# SpiderSensy_Circuitry.net
KiCad netlist of a schematic drawn in EAGLE
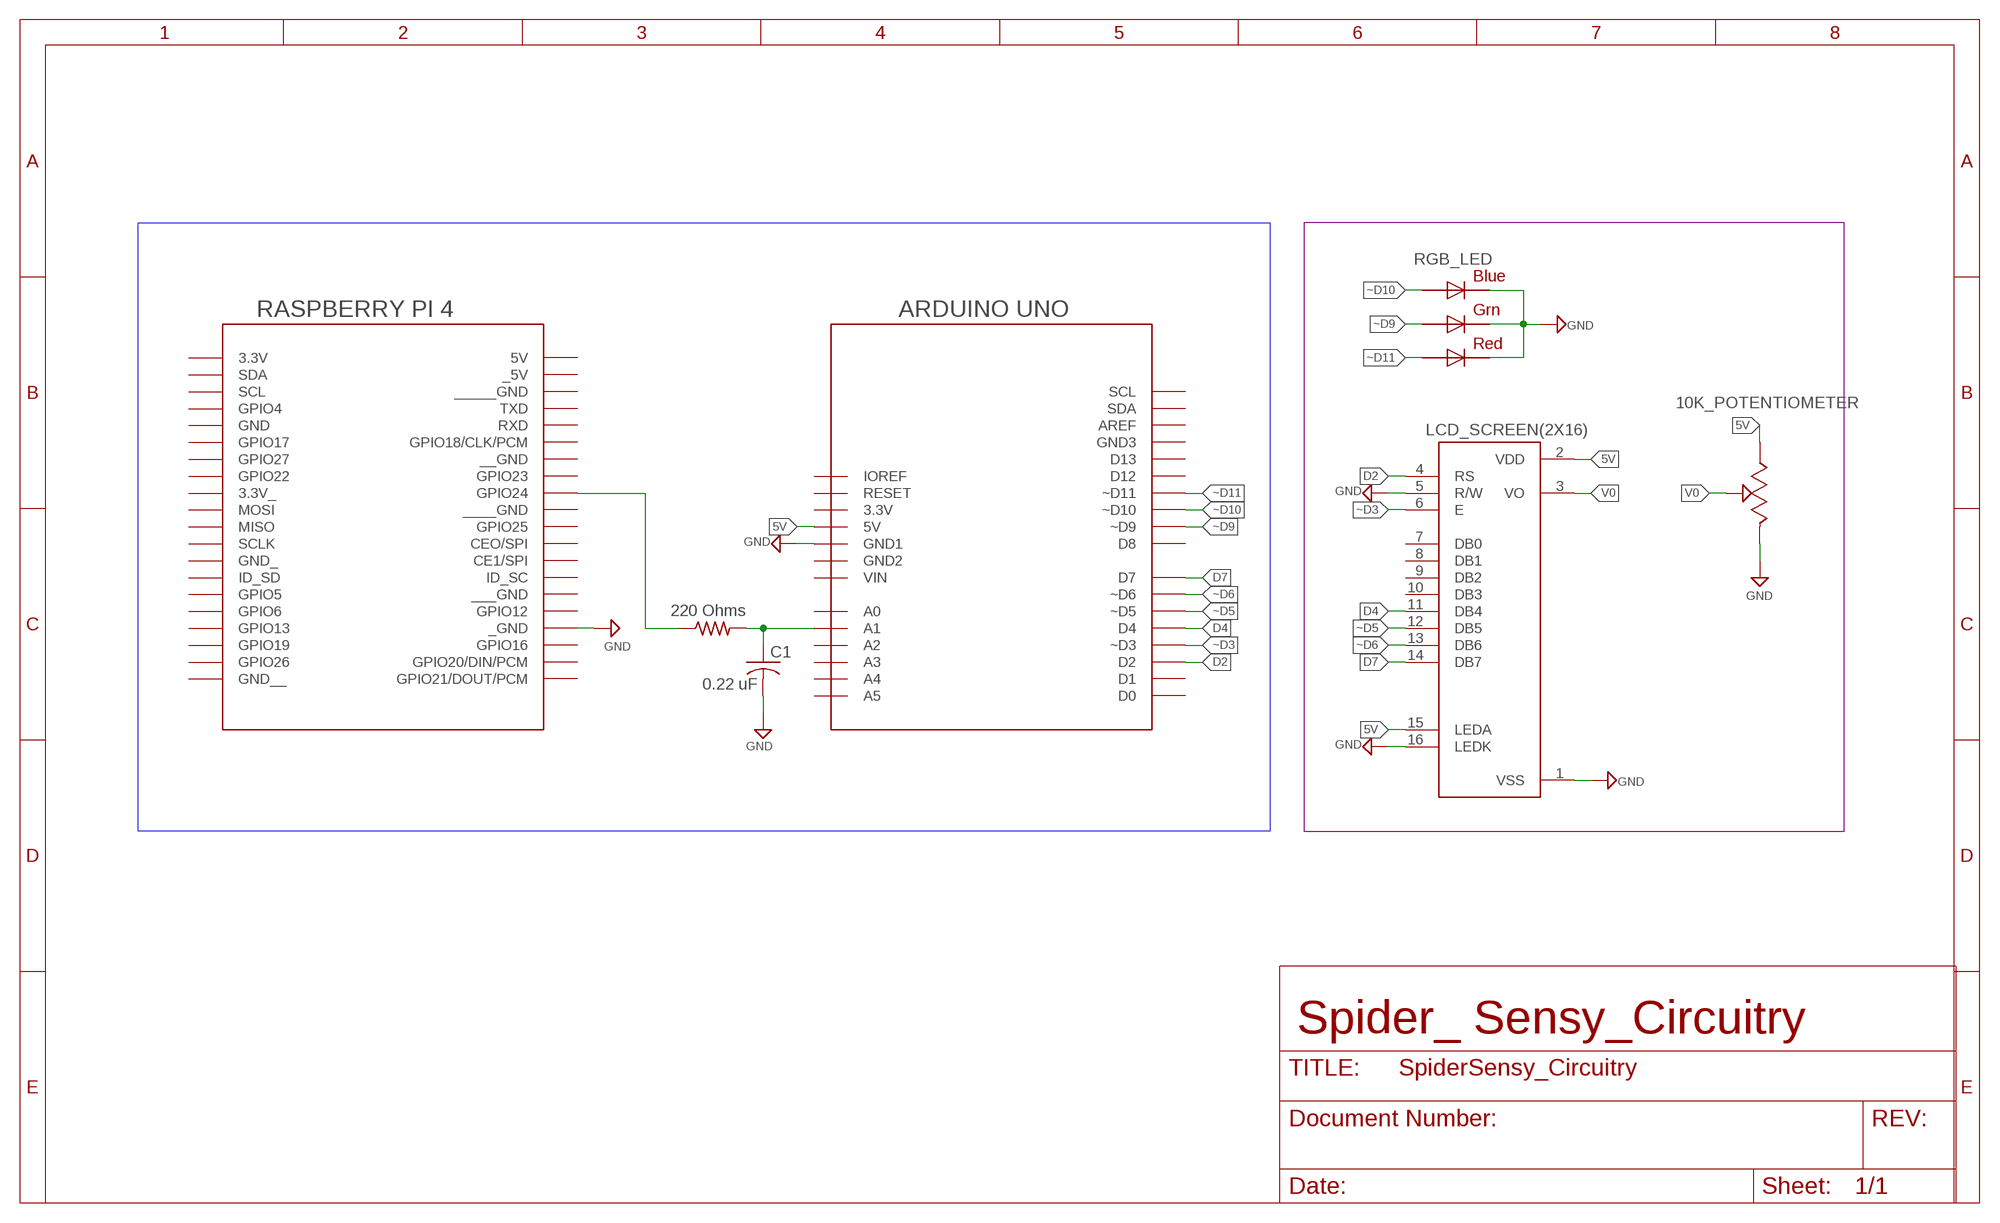
[diagram p0: schematic, sheet 1]

(export (version "E")
  (design (tool "Eeschema 10.0.6"))
  (components
    (comp (ref "10K_POTENTIOMETER")
      (value "3312J-1-103E")
      (footprint "eagle-import:TRIMMER_3312J-1-103E")
      (fields (field (name "MF") "Bourns"))
      (libsource (lib "eagle-import") (part "3312J-1-103E"))
    )
    (comp (ref "C1")
      (value "0.22 uF")
      (footprint "eagle-import:C025-024X044")
      (libsource (lib "eagle-import") (part "C-US025-024X044"))
    )
    (comp (ref "LCD_SCREEN(2X16)")
      (value "LCD2X16_16026_16X2_BYG_5V")
      (footprint "eagle-import:LCD_LCD2X16")
      (fields (field (name "MF") "mikroElektronika") (field (name "MP") "LCD2X16"))
      (libsource (lib "eagle-import") (part "LCD2X16_16026_16X2_BYG_5V"))
    )
    (comp (ref "R1")
      (value "220 Ohms")
      (footprint "eagle-import:R0805")
      (libsource (lib "eagle-import") (part "R-US_R0805"))
    )
    (comp (ref "RGB_LED")
      (value "RGBLED5050")
      (footprint "eagle-import:RGBLED5050")
      (libsource (lib "eagle-import") (part "RGBLED5050"))
    )
    (comp (ref "U$1")
      (value "ARDUINO_UNO")
      (footprint "eagle-import:ARDUINO_UNO")
      (libsource (lib "eagle-import") (part "ARDUINO_UNO"))
    )
    (comp (ref "U$3")
      (value "RASPBERRYPI")
      (footprint "eagle-import:RASPBERRY_PI")
      (libsource (lib "eagle-import") (part "RASPBERRYPI"))
    )
  )
  (nets
    (net (code "1") (name "/~{D3}") (class "Default")
      (node (ref "LCD_SCREEN(2X16)") (pin "6") (pinfunction "E_6") (pintype "input"))
      (node (ref "U$1") (pin "P$26") (pinfunction "~{D3}_P$26") (pintype "bidirectional"))
    )
    (net (code "2") (name "/~{D5}") (class "Default")
      (node (ref "LCD_SCREEN(2X16)") (pin "12") (pinfunction "DB5_12") (pintype "bidirectional"))
      (node (ref "U$1") (pin "P$27") (pinfunction "~{D5}_P$27") (pintype "bidirectional"))
    )
    (net (code "3") (name "/~{D6}") (class "Default")
      (node (ref "LCD_SCREEN(2X16)") (pin "13") (pinfunction "DB6_13") (pintype "bidirectional"))
      (node (ref "U$1") (pin "P$28") (pinfunction "~{D6}_P$28") (pintype "bidirectional"))
    )
    (net (code "4") (name "/~{D9}") (class "Default")
      (node (ref "RGB_LED") (pin "1") (pinfunction "GREEN_A_1") (pintype "bidirectional"))
      (node (ref "U$1") (pin "P$29") (pinfunction "~{D9}_P$29") (pintype "bidirectional"))
    )
    (net (code "5") (name "/~{D10}") (class "Default")
      (node (ref "RGB_LED") (pin "3") (pinfunction "BLUE_A_3") (pintype "bidirectional"))
      (node (ref "U$1") (pin "P$30") (pinfunction "~{D10}_P$30") (pintype "bidirectional"))
    )
    (net (code "6") (name "/~{D11}") (class "Default")
      (node (ref "RGB_LED") (pin "2") (pinfunction "RED_A_2") (pintype "bidirectional"))
      (node (ref "U$1") (pin "P$31") (pinfunction "~{D11}_P$31") (pintype "bidirectional"))
    )
    (net (code "7") (name "5V") (class "Default")
      (node (ref "10K_POTENTIOMETER") (pin "1") (pinfunction "CCW_1") (pintype "passive"))
      (node (ref "LCD_SCREEN(2X16)") (pin "15") (pinfunction "LEDA_15") (pintype "passive"))
      (node (ref "LCD_SCREEN(2X16)") (pin "2") (pinfunction "VDD_2") (pintype "power_in"))
      (node (ref "U$1") (pin "P$2") (pinfunction "5V_P$2") (pintype "input"))
    )
    (net (code "8") (name "D2") (class "Default")
      (node (ref "LCD_SCREEN(2X16)") (pin "4") (pinfunction "RS_4") (pintype "input"))
      (node (ref "U$1") (pin "P$12") (pinfunction "D2_P$12") (pintype "bidirectional"))
    )
    (net (code "9") (name "D4") (class "Default")
      (node (ref "LCD_SCREEN(2X16)") (pin "11") (pinfunction "DB4_11") (pintype "bidirectional"))
      (node (ref "U$1") (pin "P$13") (pinfunction "D4_P$13") (pintype "bidirectional"))
    )
    (net (code "10") (name "D7") (class "Default")
      (node (ref "LCD_SCREEN(2X16)") (pin "14") (pinfunction "DB7_14") (pintype "bidirectional"))
      (node (ref "U$1") (pin "P$14") (pinfunction "D7_P$14") (pintype "bidirectional"))
    )
    (net (code "11") (name "GND") (class "Default")
      (node (ref "10K_POTENTIOMETER") (pin "3") (pinfunction "CW_3") (pintype "passive"))
      (node (ref "C1") (pin "2") (pinfunction "2_2") (pintype "passive"))
      (node (ref "LCD_SCREEN(2X16)") (pin "1") (pinfunction "VSS_1") (pintype "power_in"))
      (node (ref "LCD_SCREEN(2X16)") (pin "16") (pinfunction "LEDK_16") (pintype "passive"))
      (node (ref "LCD_SCREEN(2X16)") (pin "5") (pinfunction "R/W_5") (pintype "input"))
      (node (ref "RGB_LED") (pin "4") (pinfunction "BLUE_C_4") (pintype "bidirectional"))
      (node (ref "RGB_LED") (pin "5") (pinfunction "RED_C_5") (pintype "bidirectional"))
      (node (ref "RGB_LED") (pin "6") (pinfunction "GREEN_C_6") (pintype "bidirectional"))
      (node (ref "U$1") (pin "P$18") (pinfunction "GND1_P$18") (pintype "bidirectional"))
      (node (ref "U$3") (pin "P$36") (pinfunction "_GND_P$36") (pintype "bidirectional"))
    )
    (net (code "12") (name "Net-(U$1-A1)") (class "Default")
      (node (ref "C1") (pin "1") (pinfunction "1_1") (pintype "passive"))
      (node (ref "R1") (pin "2") (pinfunction "2_2") (pintype "passive"))
      (node (ref "U$1") (pin "P$4") (pinfunction "A1_P$4") (pintype "bidirectional"))
    )
    (net (code "13") (name "Net-(U$3-GPIO24)") (class "Default")
      (node (ref "R1") (pin "1") (pinfunction "1_1") (pintype "passive"))
      (node (ref "U$3") (pin "P$24") (pinfunction "GPIO24_P$24") (pintype "bidirectional"))
    )
    (net (code "14") (name "V0") (class "Default")
      (node (ref "10K_POTENTIOMETER") (pin "2") (pinfunction "WIPER_2") (pintype "passive"))
      (node (ref "LCD_SCREEN(2X16)") (pin "3") (pinfunction "VO_3") (pintype "passive"))
    )
    (net (code "15") (name "unconnected-(LCD_SCREEN(2X16)-DB0-Pad7)") (class "Default")
      (node (ref "LCD_SCREEN(2X16)") (pin "7") (pinfunction "DB0_7") (pintype "bidirectional"))
    )
    (net (code "16") (name "unconnected-(LCD_SCREEN(2X16)-DB1-Pad8)") (class "Default")
      (node (ref "LCD_SCREEN(2X16)") (pin "8") (pinfunction "DB1_8") (pintype "bidirectional"))
    )
    (net (code "17") (name "unconnected-(LCD_SCREEN(2X16)-DB2-Pad9)") (class "Default")
      (node (ref "LCD_SCREEN(2X16)") (pin "9") (pinfunction "DB2_9") (pintype "bidirectional"))
    )
    (net (code "18") (name "unconnected-(LCD_SCREEN(2X16)-DB3-Pad10)") (class "Default")
      (node (ref "LCD_SCREEN(2X16)") (pin "10") (pinfunction "DB3_10") (pintype "bidirectional"))
    )
    (net (code "19") (name "unconnected-(U$1-3.3V-PadP$1)") (class "Default")
      (node (ref "U$1") (pin "P$1") (pinfunction "3.3V_P$1") (pintype "input"))
    )
    (net (code "20") (name "unconnected-(U$1-A0-PadP$3)") (class "Default")
      (node (ref "U$1") (pin "P$3") (pinfunction "A0_P$3") (pintype "bidirectional"))
    )
    (net (code "21") (name "unconnected-(U$1-A2-PadP$5)") (class "Default")
      (node (ref "U$1") (pin "P$5") (pinfunction "A2_P$5") (pintype "bidirectional"))
    )
    (net (code "22") (name "unconnected-(U$1-A3-PadP$6)") (class "Default")
      (node (ref "U$1") (pin "P$6") (pinfunction "A3_P$6") (pintype "bidirectional"))
    )
    (net (code "23") (name "unconnected-(U$1-A4-PadP$7)") (class "Default")
      (node (ref "U$1") (pin "P$7") (pinfunction "A4_P$7") (pintype "bidirectional"))
    )
    (net (code "24") (name "unconnected-(U$1-A5-PadP$8)") (class "Default")
      (node (ref "U$1") (pin "P$8") (pinfunction "A5_P$8") (pintype "bidirectional"))
    )
    (net (code "25") (name "unconnected-(U$1-AREF-PadP$9)") (class "Default")
      (node (ref "U$1") (pin "P$9") (pinfunction "AREF_P$9") (pintype "bidirectional"))
    )
    (net (code "26") (name "unconnected-(U$1-D0-PadP$10)") (class "Default")
      (node (ref "U$1") (pin "P$10") (pinfunction "D0_P$10") (pintype "bidirectional"))
    )
    (net (code "27") (name "unconnected-(U$1-D1-PadP$11)") (class "Default")
      (node (ref "U$1") (pin "P$11") (pinfunction "D1_P$11") (pintype "bidirectional"))
    )
    (net (code "28") (name "unconnected-(U$1-D8-PadP$15)") (class "Default")
      (node (ref "U$1") (pin "P$15") (pinfunction "D8_P$15") (pintype "bidirectional"))
    )
    (net (code "29") (name "unconnected-(U$1-D12-PadP$16)") (class "Default")
      (node (ref "U$1") (pin "P$16") (pinfunction "D12_P$16") (pintype "bidirectional"))
    )
    (net (code "30") (name "unconnected-(U$1-D13-PadP$17)") (class "Default")
      (node (ref "U$1") (pin "P$17") (pinfunction "D13_P$17") (pintype "bidirectional"))
    )
    (net (code "31") (name "unconnected-(U$1-GND2-PadP$19)") (class "Default")
      (node (ref "U$1") (pin "P$19") (pinfunction "GND2_P$19") (pintype "bidirectional"))
    )
    (net (code "32") (name "unconnected-(U$1-GND3-PadP$20)") (class "Default")
      (node (ref "U$1") (pin "P$20") (pinfunction "GND3_P$20") (pintype "bidirectional"))
    )
    (net (code "33") (name "unconnected-(U$1-IOREF-PadP$21)") (class "Default")
      (node (ref "U$1") (pin "P$21") (pinfunction "IOREF_P$21") (pintype "input"))
    )
    (net (code "34") (name "unconnected-(U$1-RESET-PadP$22)") (class "Default")
      (node (ref "U$1") (pin "P$22") (pinfunction "RESET_P$22") (pintype "input"))
    )
    (net (code "35") (name "unconnected-(U$1-SCL-PadP$23)") (class "Default")
      (node (ref "U$1") (pin "P$23") (pinfunction "SCL_P$23") (pintype "bidirectional"))
    )
    (net (code "36") (name "unconnected-(U$1-SDA-PadP$24)") (class "Default")
      (node (ref "U$1") (pin "P$24") (pinfunction "SDA_P$24") (pintype "bidirectional"))
    )
    (net (code "37") (name "unconnected-(U$1-VIN-PadP$25)") (class "Default")
      (node (ref "U$1") (pin "P$25") (pinfunction "VIN_P$25") (pintype "bidirectional"))
    )
    (net (code "38") (name "unconnected-(U$3-3.3V-PadP$1)") (class "Default")
      (node (ref "U$3") (pin "P$1") (pinfunction "3.3V_P$1") (pintype "input"))
    )
    (net (code "39") (name "unconnected-(U$3-3.3V_-PadP$2)") (class "Default")
      (node (ref "U$3") (pin "P$2") (pinfunction "3.3V__P$2") (pintype "bidirectional"))
    )
    (net (code "40") (name "unconnected-(U$3-5V-PadP$3)") (class "Default")
      (node (ref "U$3") (pin "P$3") (pinfunction "5V_P$3") (pintype "bidirectional"))
    )
    (net (code "41") (name "unconnected-(U$3-CE1{slash}SPI-PadP$5)") (class "Default")
      (node (ref "U$3") (pin "P$5") (pinfunction "CE1/SPI_P$5") (pintype "bidirectional"))
    )
    (net (code "42") (name "unconnected-(U$3-CEO{slash}SPI-PadP$6)") (class "Default")
      (node (ref "U$3") (pin "P$6") (pinfunction "CEO/SPI_P$6") (pintype "bidirectional"))
    )
    (net (code "43") (name "unconnected-(U$3-GND-PadP$7)") (class "Default")
      (node (ref "U$3") (pin "P$7") (pinfunction "GND_P$7") (pintype "bidirectional"))
    )
    (net (code "44") (name "unconnected-(U$3-GND_-PadP$8)") (class "Default")
      (node (ref "U$3") (pin "P$8") (pinfunction "GND__P$8") (pintype "bidirectional"))
    )
    (net (code "45") (name "unconnected-(U$3-GND__-PadP$9)") (class "Default")
      (node (ref "U$3") (pin "P$9") (pinfunction "GND___P$9") (pintype "bidirectional"))
    )
    (net (code "46") (name "unconnected-(U$3-GPIO4-PadP$10)") (class "Default")
      (node (ref "U$3") (pin "P$10") (pinfunction "GPIO4_P$10") (pintype "input"))
    )
    (net (code "47") (name "unconnected-(U$3-GPIO5-PadP$11)") (class "Default")
      (node (ref "U$3") (pin "P$11") (pinfunction "GPIO5_P$11") (pintype "bidirectional"))
    )
    (net (code "48") (name "unconnected-(U$3-GPIO6-PadP$12)") (class "Default")
      (node (ref "U$3") (pin "P$12") (pinfunction "GPIO6_P$12") (pintype "bidirectional"))
    )
    (net (code "49") (name "unconnected-(U$3-GPIO12-PadP$13)") (class "Default")
      (node (ref "U$3") (pin "P$13") (pinfunction "GPIO12_P$13") (pintype "bidirectional"))
    )
    (net (code "50") (name "unconnected-(U$3-GPIO13-PadP$14)") (class "Default")
      (node (ref "U$3") (pin "P$14") (pinfunction "GPIO13_P$14") (pintype "bidirectional"))
    )
    (net (code "51") (name "unconnected-(U$3-GPIO16-PadP$15)") (class "Default")
      (node (ref "U$3") (pin "P$15") (pinfunction "GPIO16_P$15") (pintype "bidirectional"))
    )
    (net (code "52") (name "unconnected-(U$3-GPIO17-PadP$16)") (class "Default")
      (node (ref "U$3") (pin "P$16") (pinfunction "GPIO17_P$16") (pintype "bidirectional"))
    )
    (net (code "53") (name "unconnected-(U$3-GPIO18{slash}CLK{slash}PCM-PadP$18)") (class "Default")
      (node (ref "U$3") (pin "P$18") (pinfunction "GPIO18/CLK/PCM_P$18") (pintype "bidirectional"))
    )
    (net (code "54") (name "unconnected-(U$3-GPIO19-PadP$17)") (class "Default")
      (node (ref "U$3") (pin "P$17") (pinfunction "GPIO19_P$17") (pintype "bidirectional"))
    )
    (net (code "55") (name "unconnected-(U$3-GPIO20{slash}DIN{slash}PCM-PadP$20)") (class "Default")
      (node (ref "U$3") (pin "P$20") (pinfunction "GPIO20/DIN/PCM_P$20") (pintype "bidirectional"))
    )
    (net (code "56") (name "unconnected-(U$3-GPIO21{slash}DOUT{slash}PCM-PadP$21)") (class "Default")
      (node (ref "U$3") (pin "P$21") (pinfunction "GPIO21/DOUT/PCM_P$21") (pintype "bidirectional"))
    )
    (net (code "57") (name "unconnected-(U$3-GPIO22-PadP$22)") (class "Default")
      (node (ref "U$3") (pin "P$22") (pinfunction "GPIO22_P$22") (pintype "bidirectional"))
    )
    (net (code "58") (name "unconnected-(U$3-GPIO23-PadP$23)") (class "Default")
      (node (ref "U$3") (pin "P$23") (pinfunction "GPIO23_P$23") (pintype "bidirectional"))
    )
    (net (code "59") (name "unconnected-(U$3-GPIO25-PadP$25)") (class "Default")
      (node (ref "U$3") (pin "P$25") (pinfunction "GPIO25_P$25") (pintype "bidirectional"))
    )
    (net (code "60") (name "unconnected-(U$3-GPIO26-PadP$19)") (class "Default")
      (node (ref "U$3") (pin "P$19") (pinfunction "GPIO26_P$19") (pintype "bidirectional"))
    )
    (net (code "61") (name "unconnected-(U$3-GPIO27-PadP$26)") (class "Default")
      (node (ref "U$3") (pin "P$26") (pinfunction "GPIO27_P$26") (pintype "bidirectional"))
    )
    (net (code "62") (name "unconnected-(U$3-ID_SC-PadP$27)") (class "Default")
      (node (ref "U$3") (pin "P$27") (pinfunction "ID_SC_P$27") (pintype "bidirectional"))
    )
    (net (code "63") (name "unconnected-(U$3-ID_SD-PadP$28)") (class "Default")
      (node (ref "U$3") (pin "P$28") (pinfunction "ID_SD_P$28") (pintype "bidirectional"))
    )
    (net (code "64") (name "unconnected-(U$3-MISO-PadP$29)") (class "Default")
      (node (ref "U$3") (pin "P$29") (pinfunction "MISO_P$29") (pintype "bidirectional"))
    )
    (net (code "65") (name "unconnected-(U$3-MOSI-PadP$30)") (class "Default")
      (node (ref "U$3") (pin "P$30") (pinfunction "MOSI_P$30") (pintype "bidirectional"))
    )
    (net (code "66") (name "unconnected-(U$3-RXD-PadP$31)") (class "Default")
      (node (ref "U$3") (pin "P$31") (pinfunction "RXD_P$31") (pintype "bidirectional"))
    )
    (net (code "67") (name "unconnected-(U$3-SCL-PadP$32)") (class "Default")
      (node (ref "U$3") (pin "P$32") (pinfunction "SCL_P$32") (pintype "input"))
    )
    (net (code "68") (name "unconnected-(U$3-SCLK-PadP$33)") (class "Default")
      (node (ref "U$3") (pin "P$33") (pinfunction "SCLK_P$33") (pintype "bidirectional"))
    )
    (net (code "69") (name "unconnected-(U$3-SDA-PadP$34)") (class "Default")
      (node (ref "U$3") (pin "P$34") (pinfunction "SDA_P$34") (pintype "input"))
    )
    (net (code "70") (name "unconnected-(U$3-TXD-PadP$35)") (class "Default")
      (node (ref "U$3") (pin "P$35") (pinfunction "TXD_P$35") (pintype "bidirectional"))
    )
    (net (code "71") (name "unconnected-(U$3-_5V-PadP$4)") (class "Default")
      (node (ref "U$3") (pin "P$4") (pinfunction "_5V_P$4") (pintype "bidirectional"))
    )
    (net (code "72") (name "unconnected-(U$3-__GND-PadP$37)") (class "Default")
      (node (ref "U$3") (pin "P$37") (pinfunction "__GND_P$37") (pintype "bidirectional"))
    )
    (net (code "73") (name "unconnected-(U$3-___GND-PadP$38)") (class "Default")
      (node (ref "U$3") (pin "P$38") (pinfunction "___GND_P$38") (pintype "bidirectional"))
    )
    (net (code "74") (name "unconnected-(U$3-____GND-PadP$39)") (class "Default")
      (node (ref "U$3") (pin "P$39") (pinfunction "____GND_P$39") (pintype "bidirectional"))
    )
    (net (code "75") (name "unconnected-(U$3-_____GND-PadP$40)") (class "Default")
      (node (ref "U$3") (pin "P$40") (pinfunction "_____GND_P$40") (pintype "bidirectional"))
    )
  )
)
